# STM32F407layout.net
KiCad netlist of a schematic drawn in EAGLE
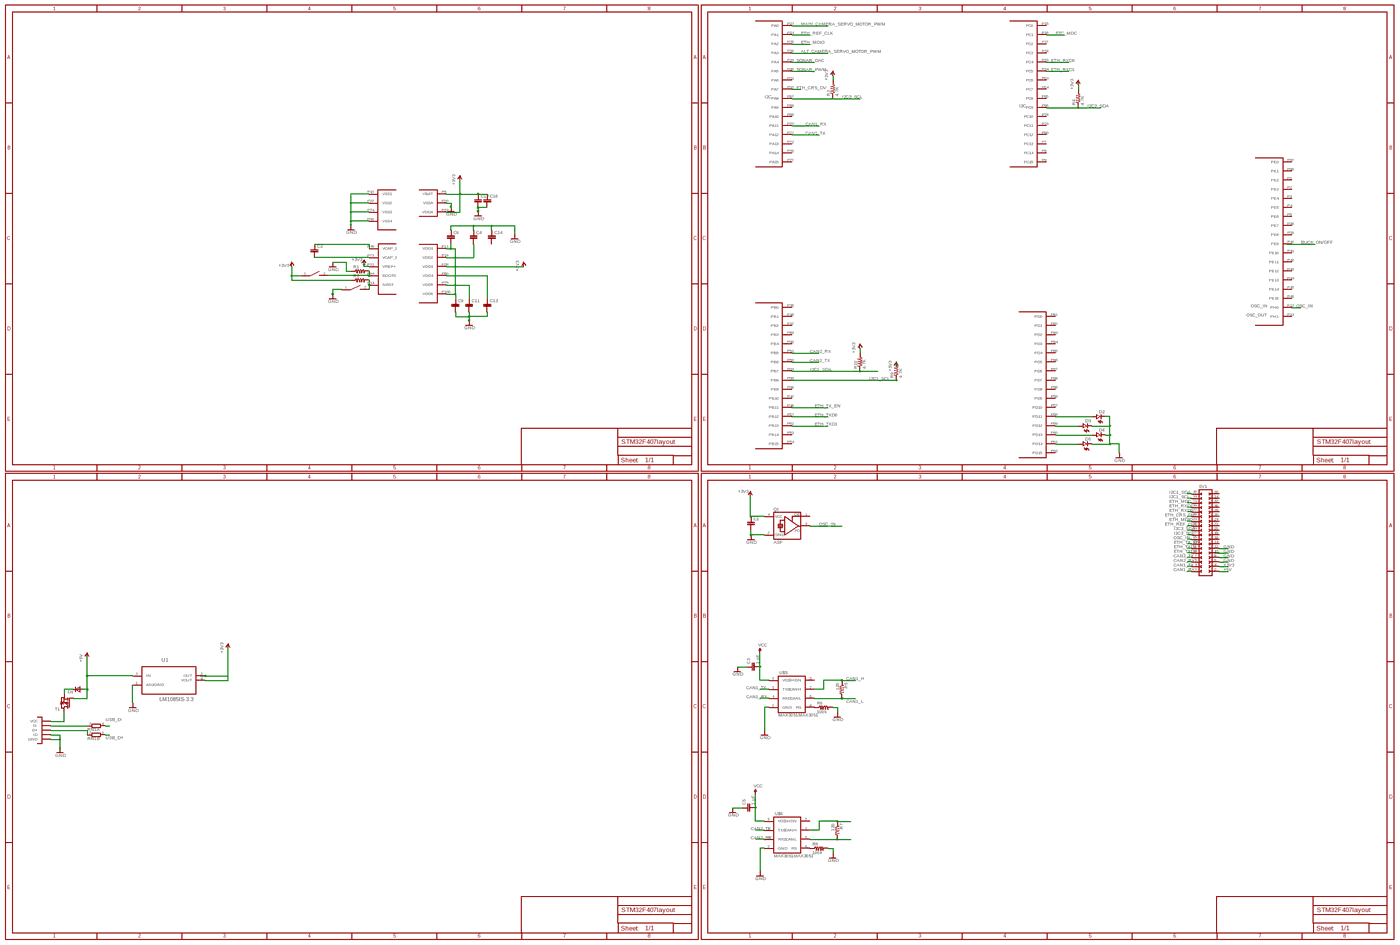
[diagram p0: schematic, sheet 1, overview]
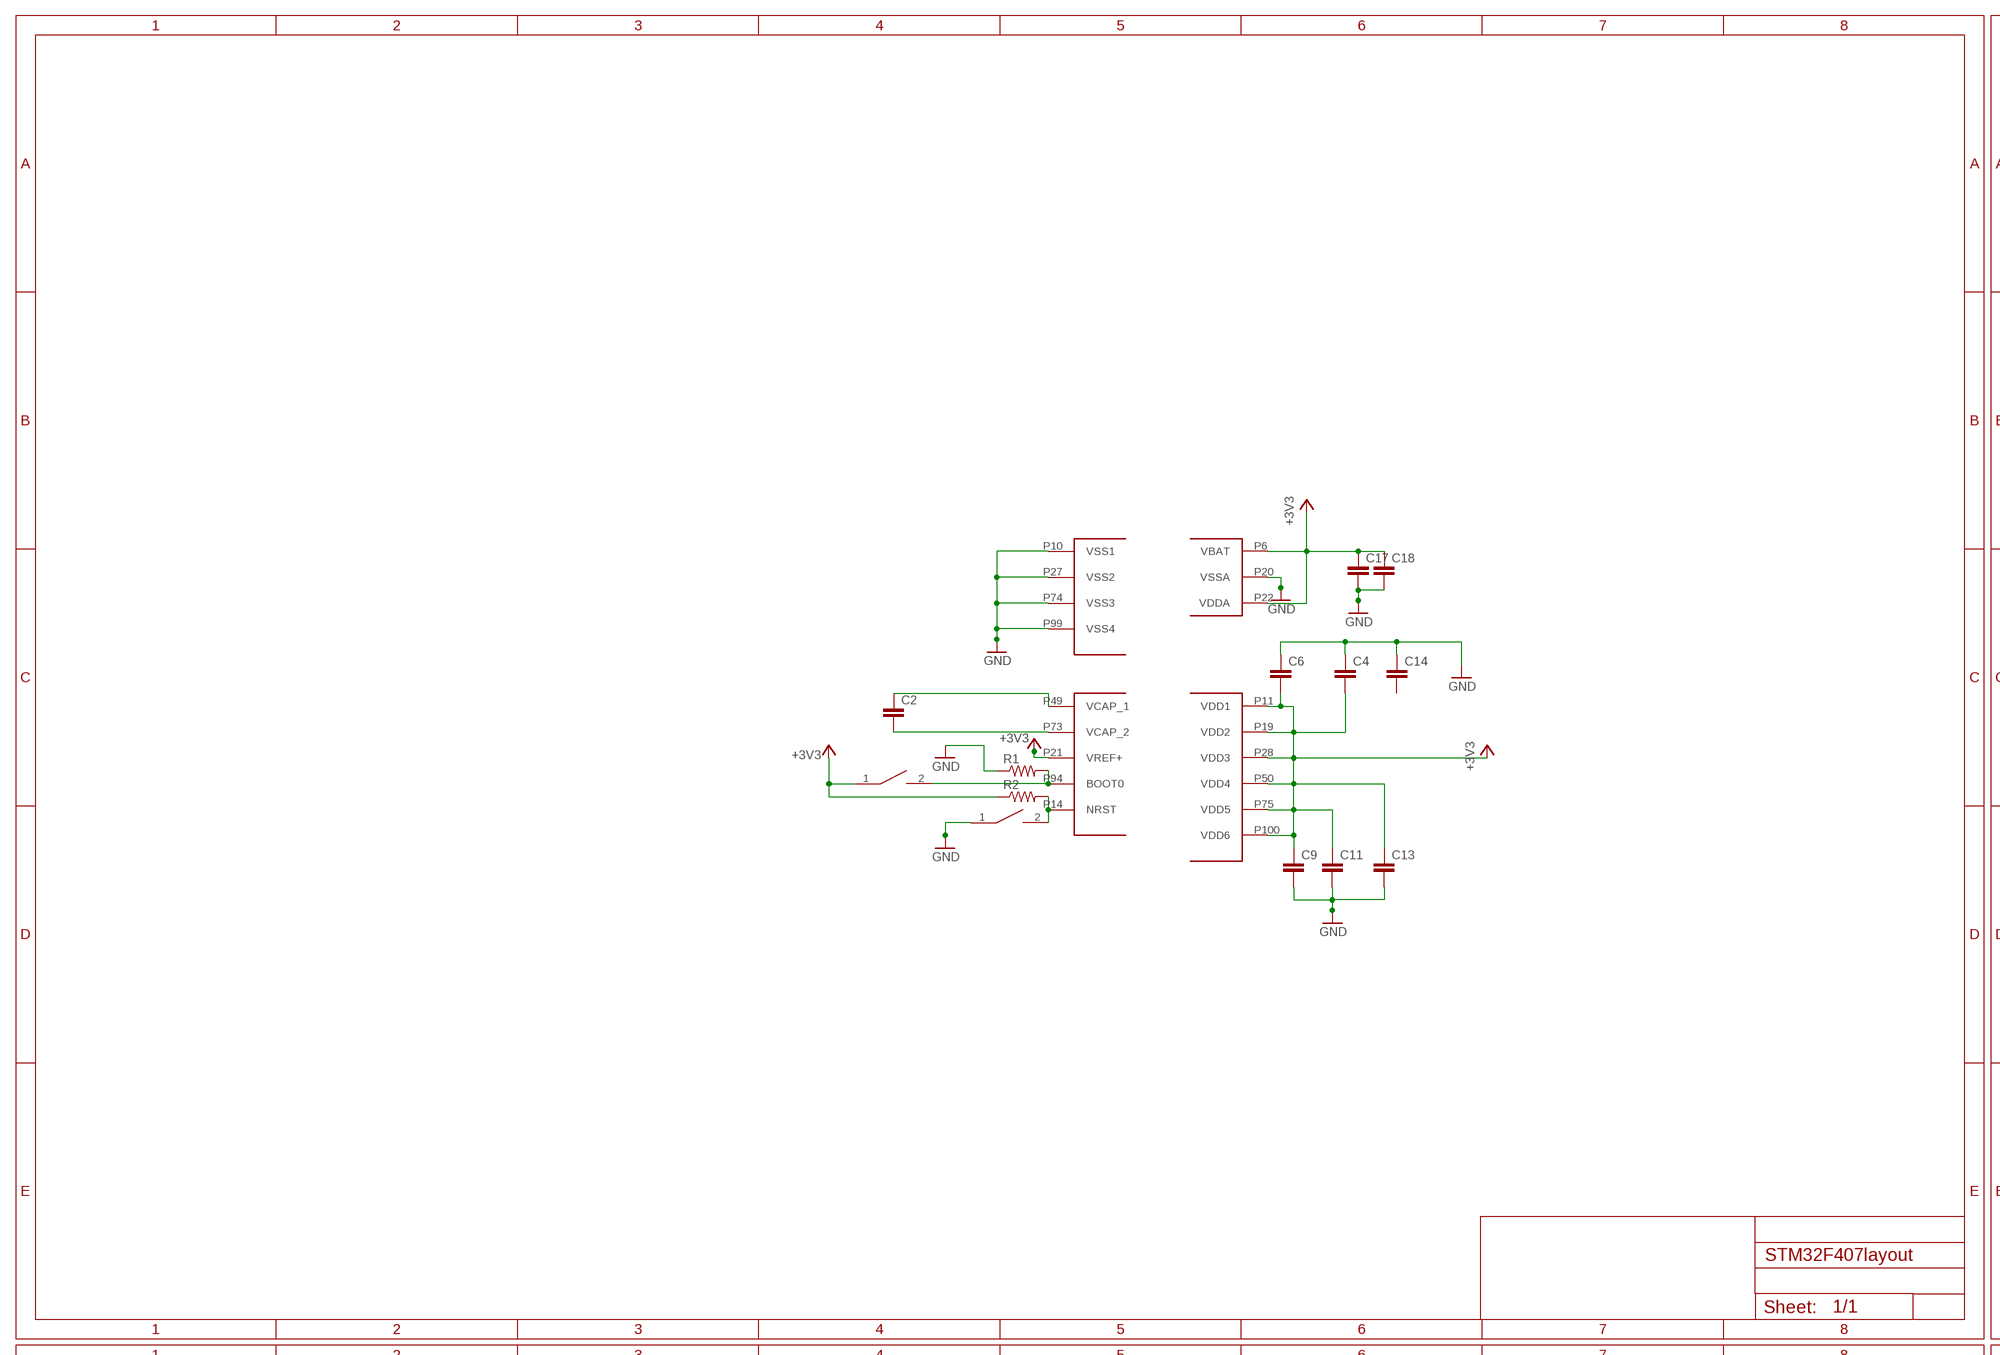
[diagram p1: schematic, sheet 1, part 1 of 4]
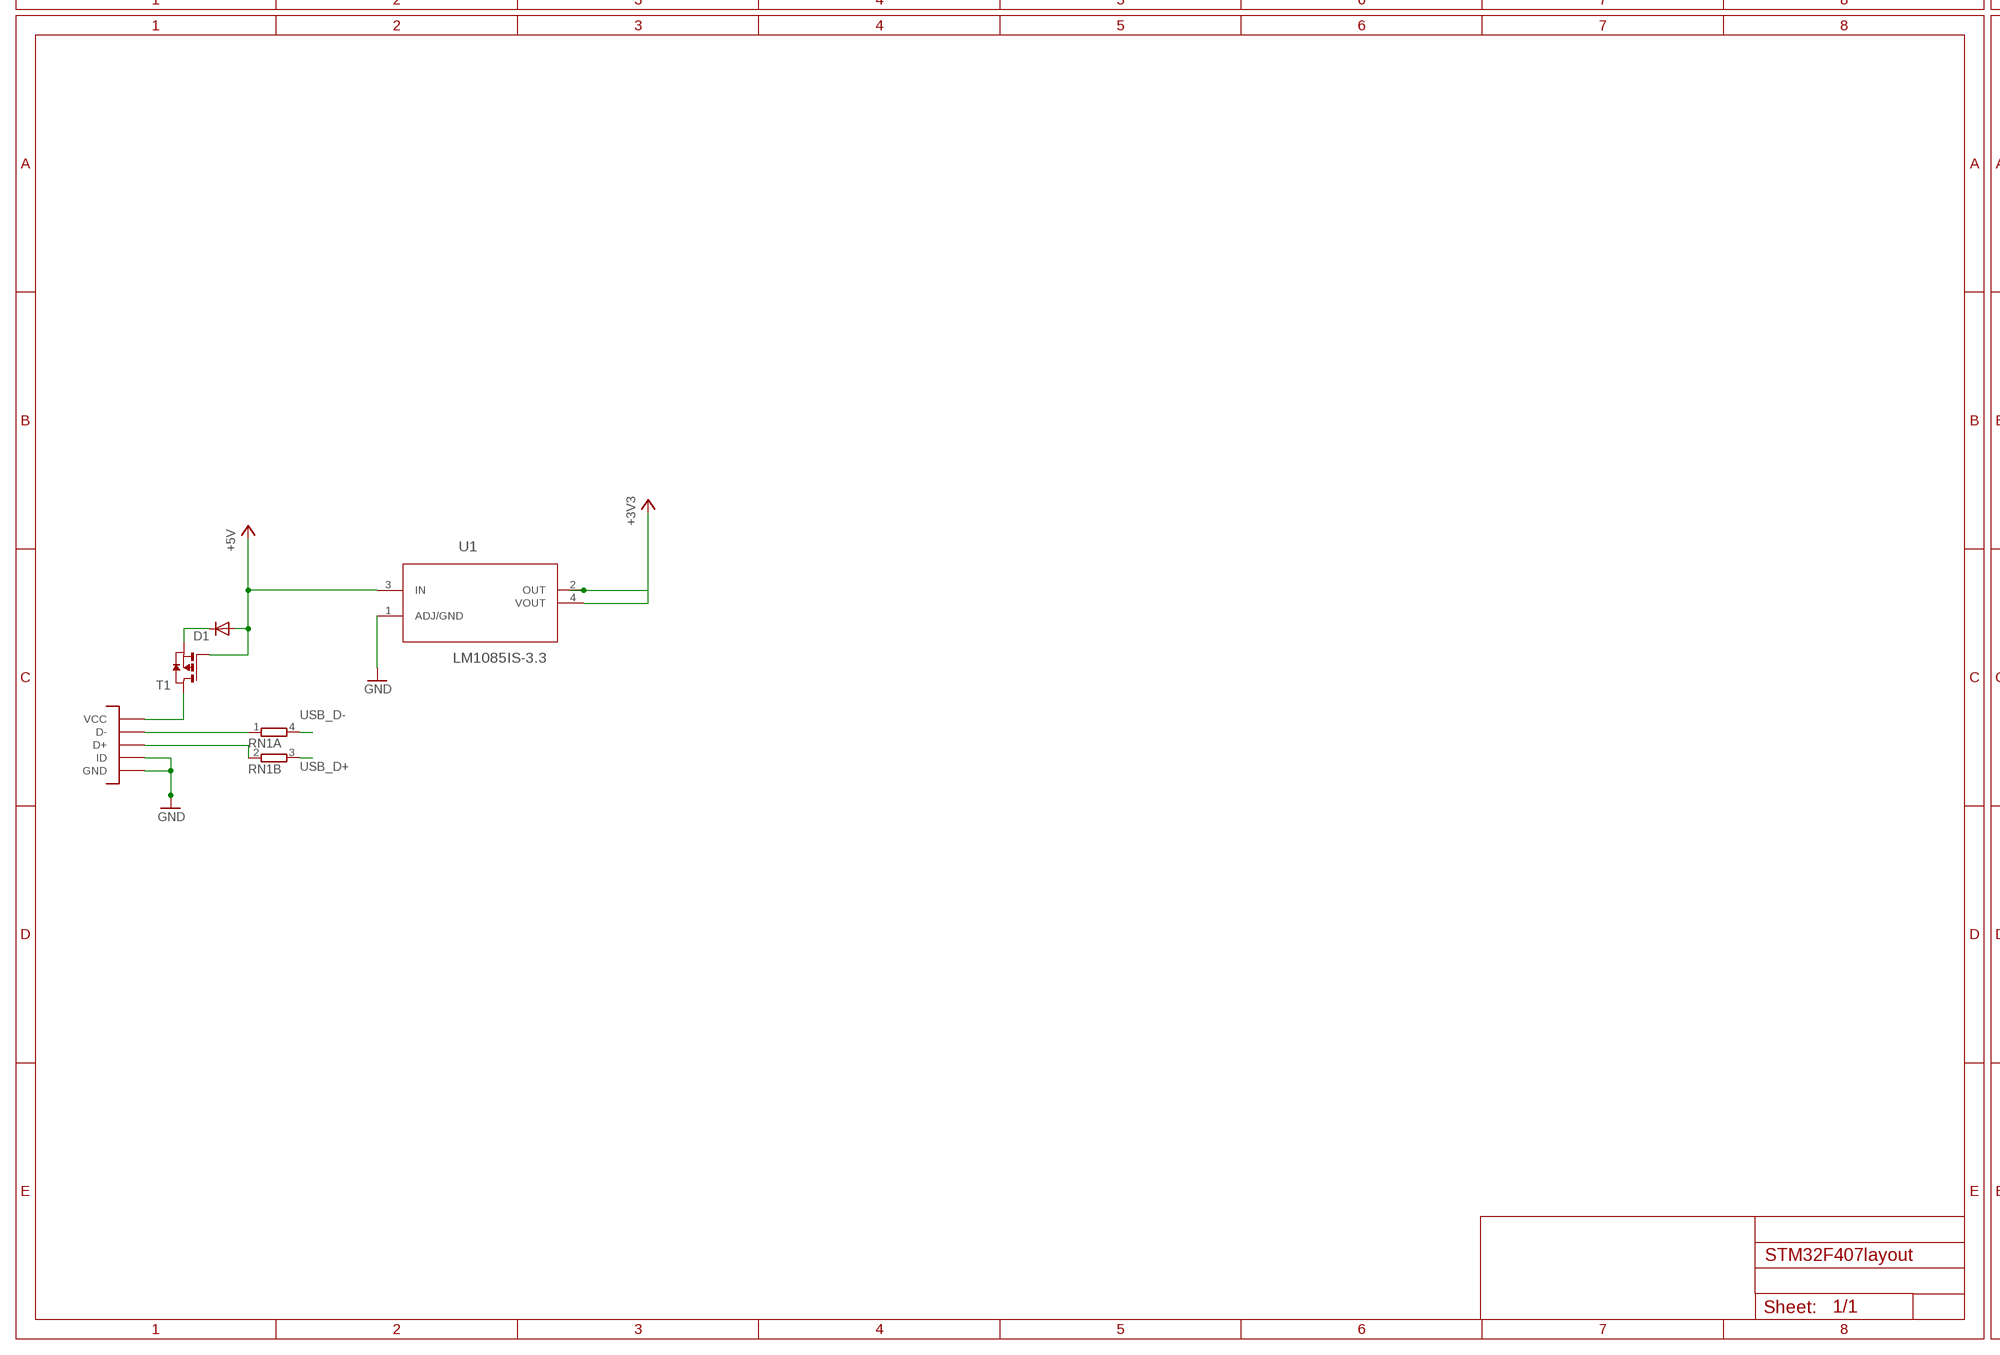
[diagram p2: schematic, sheet 1, part 2 of 4]
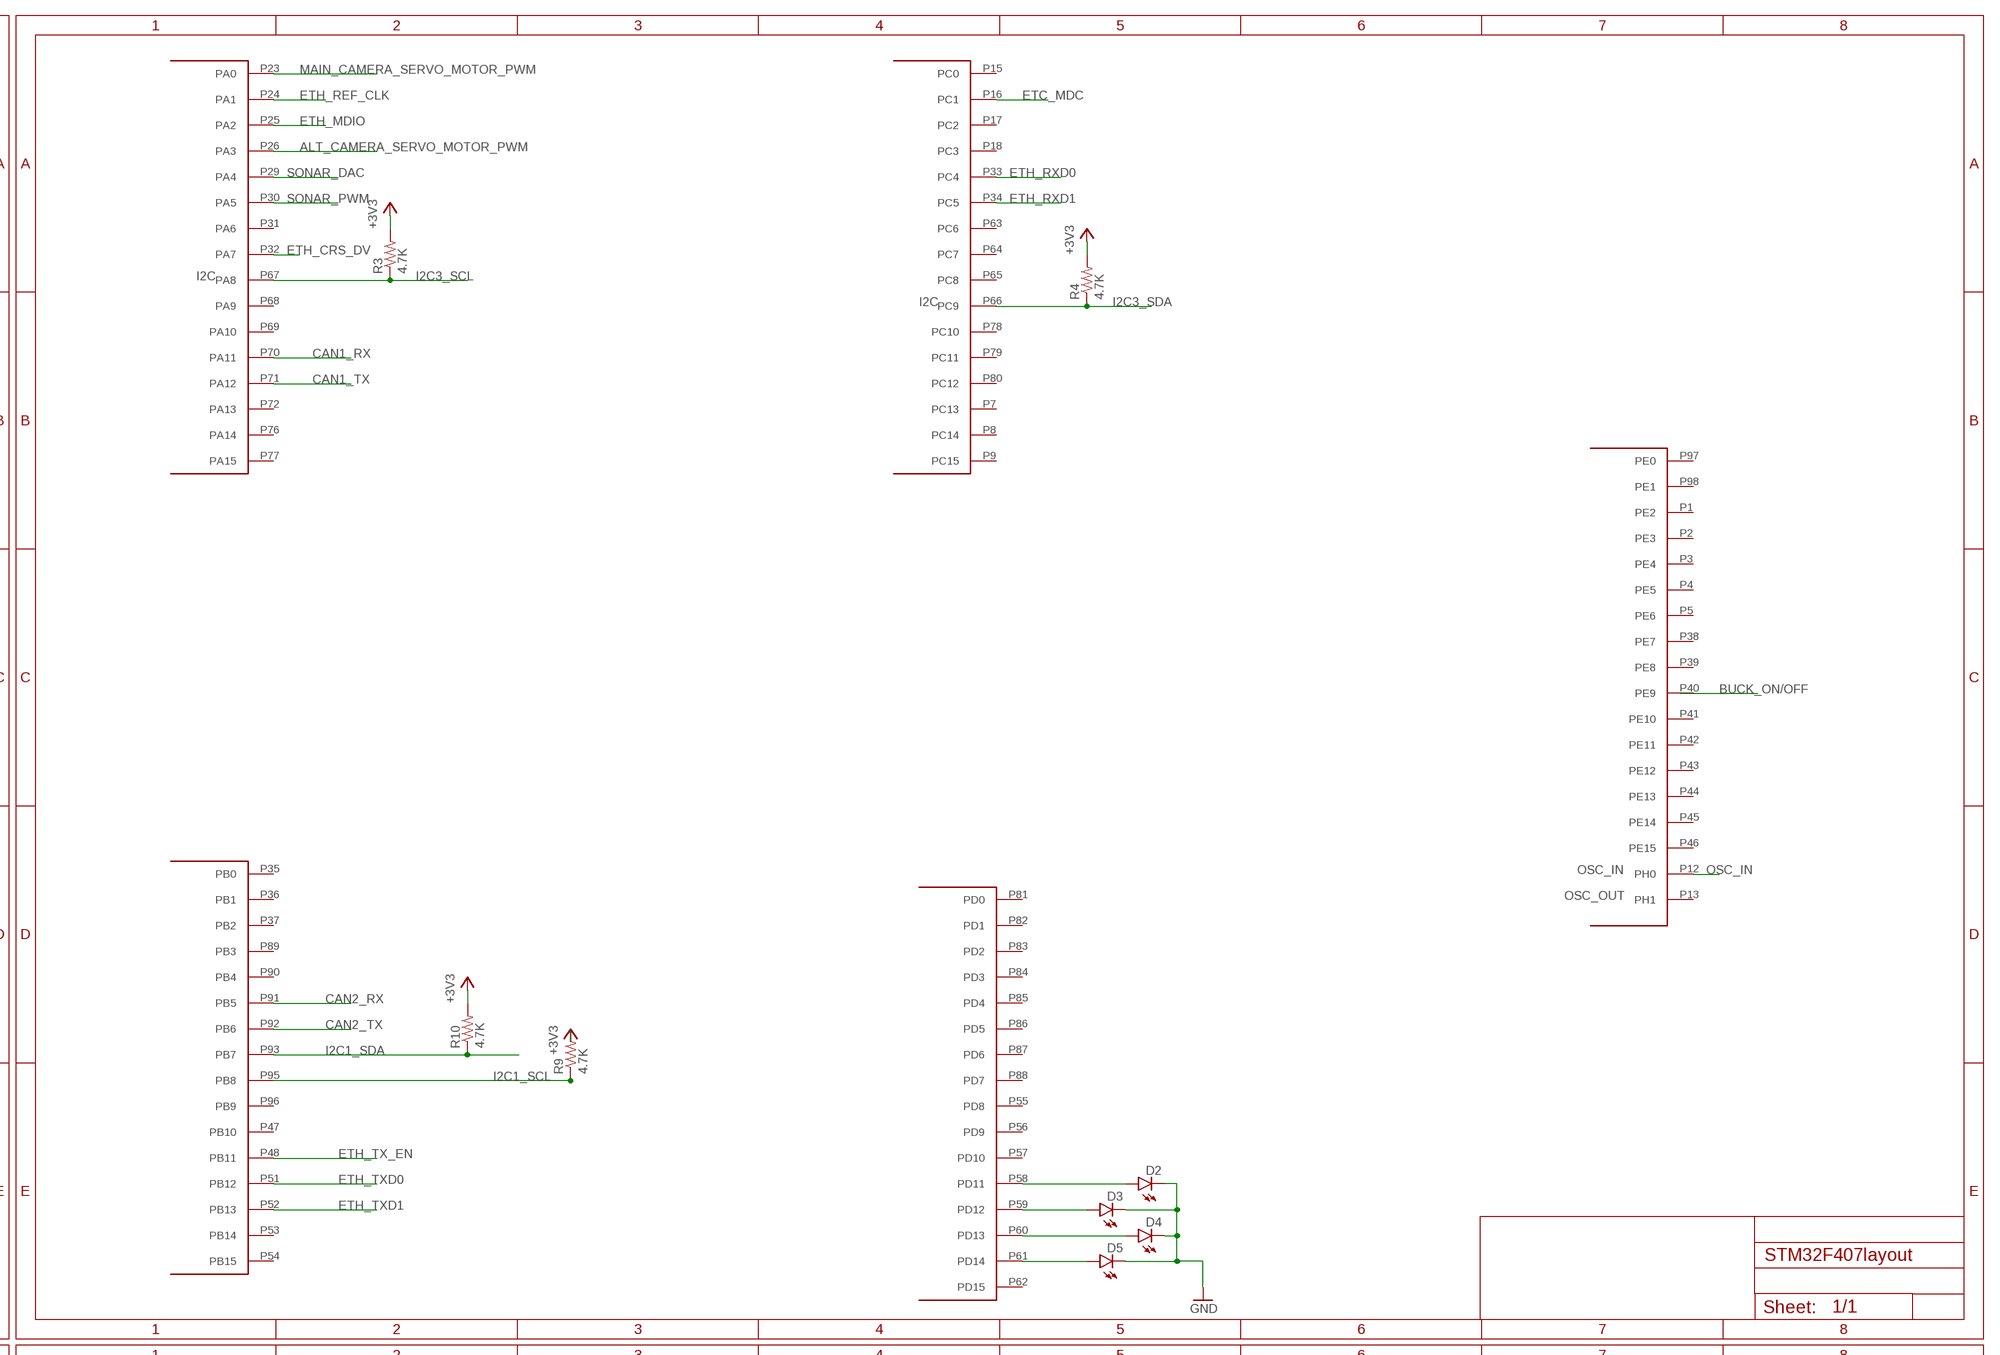
[diagram p3: schematic, sheet 1, part 3 of 4]
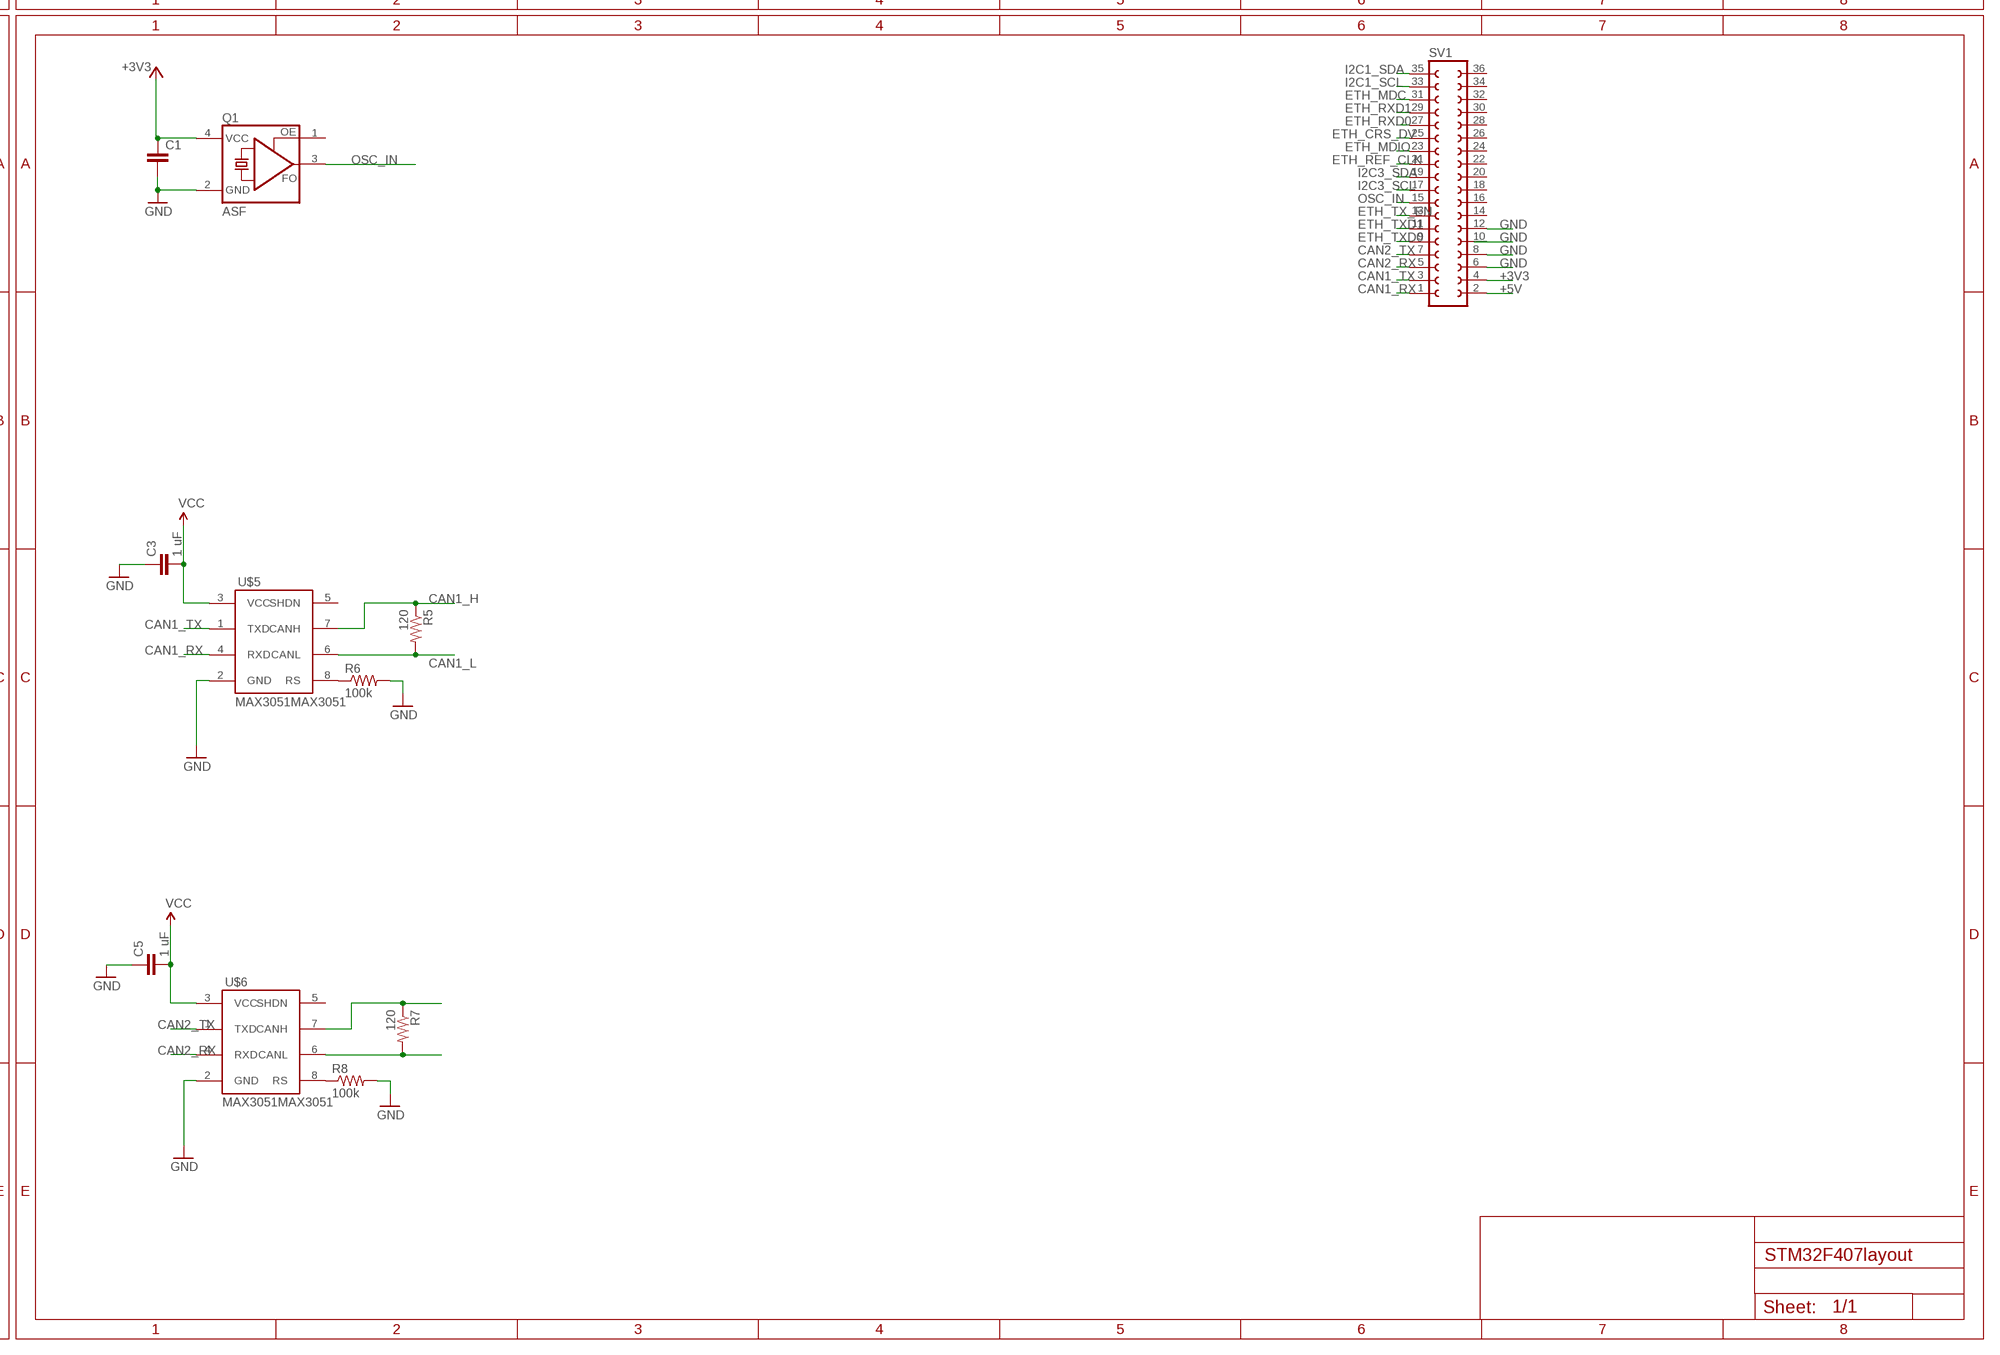
[diagram p4: schematic, sheet 1, part 4 of 4]

(export (version "E")
  (design (tool "Eeschema 10.0.6"))
  (components
    (comp (ref "C1")
      (value "CAP0603-CAP")
      (footprint "eagle-import:0603-CAP")
      (libsource (lib "eagle-import") (part "CAP0603-CAP"))
    )
    (comp (ref "C2")
      (value "CAP0603-CAP")
      (footprint "eagle-import:0603-CAP")
      (libsource (lib "eagle-import") (part "CAP0603-CAP"))
    )
    (comp (ref "C3")
      (value "1 uF")
      (footprint "eagle-import:C2.5-3")
      (libsource (lib "eagle-import") (part "C2,5-3"))
    )
    (comp (ref "C4")
      (value "CAP0603-CAP")
      (footprint "eagle-import:0603-CAP")
      (libsource (lib "eagle-import") (part "CAP0603-CAP"))
    )
    (comp (ref "C5")
      (value "1 uF")
      (footprint "eagle-import:C2.5-3")
      (libsource (lib "eagle-import") (part "C2,5-3"))
    )
    (comp (ref "C6")
      (value "CAP0603-CAP")
      (footprint "eagle-import:0603-CAP")
      (libsource (lib "eagle-import") (part "CAP0603-CAP"))
    )
    (comp (ref "C9")
      (value "CAP0603-CAP")
      (footprint "eagle-import:0603-CAP")
      (libsource (lib "eagle-import") (part "CAP0603-CAP"))
    )
    (comp (ref "C11")
      (value "CAP0603-CAP")
      (footprint "eagle-import:0603-CAP")
      (libsource (lib "eagle-import") (part "CAP0603-CAP"))
    )
    (comp (ref "C13")
      (value "CAP0603-CAP")
      (footprint "eagle-import:0603-CAP")
      (libsource (lib "eagle-import") (part "CAP0603-CAP"))
    )
    (comp (ref "C14")
      (value "CAP0603-CAP")
      (footprint "eagle-import:0603-CAP")
      (libsource (lib "eagle-import") (part "CAP0603-CAP"))
    )
    (comp (ref "C17")
      (value "CAP0603-CAP")
      (footprint "eagle-import:0603-CAP")
      (libsource (lib "eagle-import") (part "CAP0603-CAP"))
    )
    (comp (ref "C18")
      (value "CAP0603-CAP")
      (footprint "eagle-import:0603-CAP")
      (libsource (lib "eagle-import") (part "CAP0603-CAP"))
    )
    (comp (ref "D1")
      (value "DIODE-DO-214AC")
      (footprint "eagle-import:DO-214AC")
      (libsource (lib "eagle-import") (part "DIODE-DO-214AC"))
    )
    (comp (ref "D2")
      (value "LED0603")
      (footprint "eagle-import:LED-0603")
      (libsource (lib "eagle-import") (part "LED0603"))
    )
    (comp (ref "D3")
      (value "LED0603")
      (footprint "eagle-import:LED-0603")
      (libsource (lib "eagle-import") (part "LED0603"))
    )
    (comp (ref "D4")
      (value "LED0603")
      (footprint "eagle-import:LED-0603")
      (libsource (lib "eagle-import") (part "LED0603"))
    )
    (comp (ref "D5")
      (value "LED0603")
      (footprint "eagle-import:LED-0603")
      (libsource (lib "eagle-import") (part "LED0603"))
    )
    (comp (ref "Q1")
      (value "ASF")
      (footprint "eagle-import:ASF")
      (libsource (lib "eagle-import") (part "ASF"))
    )
    (comp (ref "R1")
      (value "RESISTOR0603-RES")
      (footprint "eagle-import:0603-RES")
      (libsource (lib "eagle-import") (part "RESISTOR0603-RES"))
    )
    (comp (ref "R2")
      (value "RESISTOR0603-RES")
      (footprint "eagle-import:0603-RES")
      (libsource (lib "eagle-import") (part "RESISTOR0603-RES"))
    )
    (comp (ref "R3")
      (value "4.7K")
      (footprint "eagle-import:0603-RES")
      (libsource (lib "eagle-import") (part "RESISTOR0603-RES"))
    )
    (comp (ref "R4")
      (value "4.7K")
      (footprint "eagle-import:0603-RES")
      (libsource (lib "eagle-import") (part "RESISTOR0603-RES"))
    )
    (comp (ref "R5")
      (value "120")
      (footprint "eagle-import:0204V")
      (libsource (lib "eagle-import") (part "R-US_0204/2V"))
    )
    (comp (ref "R6")
      (value "100k")
      (footprint "eagle-import:0204V")
      (libsource (lib "eagle-import") (part "R-US_0204/2V"))
    )
    (comp (ref "R7")
      (value "120")
      (footprint "eagle-import:0204V")
      (libsource (lib "eagle-import") (part "R-US_0204/2V"))
    )
    (comp (ref "R8")
      (value "100k")
      (footprint "eagle-import:0204V")
      (libsource (lib "eagle-import") (part "R-US_0204/2V"))
    )
    (comp (ref "R9")
      (value "4.7K")
      (footprint "eagle-import:0603-RES")
      (libsource (lib "eagle-import") (part "RESISTOR0603-RES"))
    )
    (comp (ref "R10")
      (value "4.7K")
      (footprint "eagle-import:0603-RES")
      (libsource (lib "eagle-import") (part "RESISTOR0603-RES"))
    )
    (comp (ref "RN1")
      (value "2R-NEXBV4V")
      (footprint "eagle-import:EXBV4V")
      (fields (field (name "MF") "Rohm Semiconductor") (field (name "MPN") "MNR12ERAPJ220"))
      (libsource (lib "eagle-import") (part "2R-NEXBV4V"))
    )
    (comp (ref "SV1")
      (value "FE18-2")
      (footprint "eagle-import:FE18-2")
      (libsource (lib "eagle-import") (part "FE18-2"))
    )
    (comp (ref "T1")
      (value "FDN340P")
      (footprint "eagle-import:SOT-23")
      (libsource (lib "eagle-import") (part "FDN340P"))
    )
    (comp (ref "U$1")
      (value "STM32F4")
      (footprint "eagle-import:LQFP100")
      (libsource (lib "eagle-import") (part "STM32F4"))
    )
    (comp (ref "U$2")
      (value "SWITCH")
      (footprint "eagle-import:SW_2512")
      (libsource (lib "eagle-import") (part "SWITCH"))
    )
    (comp (ref "U$3")
      (value "SWITCH")
      (footprint "eagle-import:SW_2512")
      (libsource (lib "eagle-import") (part "SWITCH"))
    )
    (comp (ref "U$4")
      (value "MICROUSB")
      (footprint "eagle-import:MICRO_B")
      (libsource (lib "eagle-import") (part "MICROUSB"))
    )
    (comp (ref "U$5")
      (value "MAX3051MAX3051")
      (footprint "eagle-import:SOT23-8L")
      (libsource (lib "eagle-import") (part "MAX3051MAX3051"))
    )
    (comp (ref "U$6")
      (value "MAX3051MAX3051")
      (footprint "eagle-import:SOT23-8L")
      (libsource (lib "eagle-import") (part "MAX3051MAX3051"))
    )
    (comp (ref "U1")
      (value "LM1085IS-3.3")
      (footprint "eagle-import:TO254P1435X457-3N")
      (libsource (lib "eagle-import") (part "LM1085IS-3.3"))
    )
  )
  (nets
    (net (code "1") (name "+3V3") (class "Default")
      (node (ref "C11") (pin "1") (pinfunction "1_1") (pintype "passive"))
      (node (ref "C13") (pin "1") (pinfunction "1_1") (pintype "passive"))
      (node (ref "C17") (pin "1") (pinfunction "1_1") (pintype "passive"))
      (node (ref "C18") (pin "1") (pinfunction "1_1") (pintype "passive"))
      (node (ref "C4") (pin "2") (pinfunction "2_2") (pintype "passive"))
      (node (ref "C6") (pin "2") (pinfunction "2_2") (pintype "passive"))
      (node (ref "C9") (pin "1") (pinfunction "1_1") (pintype "passive"))
      (node (ref "R10") (pin "2") (pinfunction "2_2") (pintype "passive"))
      (node (ref "R2") (pin "1") (pinfunction "1_1") (pintype "passive"))
      (node (ref "R3") (pin "2") (pinfunction "2_2") (pintype "passive"))
      (node (ref "R4") (pin "2") (pinfunction "2_2") (pintype "passive"))
      (node (ref "R9") (pin "2") (pinfunction "2_2") (pintype "passive"))
      (node (ref "SV1") (pin "4") (pinfunction "4_4") (pintype "passive"))
      (node (ref "U$1") (pin "P100") (pinfunction "VDD6_P100") (pintype "bidirectional"))
      (node (ref "U$1") (pin "P11") (pinfunction "VDD1_P11") (pintype "bidirectional"))
      (node (ref "U$1") (pin "P19") (pinfunction "VDD2_P19") (pintype "bidirectional"))
      (node (ref "U$1") (pin "P21") (pinfunction "VREF+_P21") (pintype "bidirectional"))
      (node (ref "U$1") (pin "P22") (pinfunction "VDDA_P22") (pintype "bidirectional"))
      (node (ref "U$1") (pin "P28") (pinfunction "VDD3_P28") (pintype "bidirectional"))
      (node (ref "U$1") (pin "P50") (pinfunction "VDD4_P50") (pintype "bidirectional"))
      (node (ref "U$1") (pin "P6") (pinfunction "VBAT_P6") (pintype "bidirectional"))
      (node (ref "U$1") (pin "P75") (pinfunction "VDD5_P75") (pintype "bidirectional"))
      (node (ref "U$3") (pin "1") (pinfunction "P$1_1") (pintype "bidirectional"))
      (node (ref "U1") (pin "2") (pinfunction "OUT_2") (pintype "output"))
      (node (ref "U1") (pin "4") (pinfunction "VOUT_4") (pintype "output"))
    )
    (net (code "2") (name "+5V") (class "Default")
      (node (ref "D1") (pin "A") (pinfunction "A_A") (pintype "passive"))
      (node (ref "SV1") (pin "2") (pinfunction "2_2") (pintype "passive"))
      (node (ref "T1") (pin "3") (pinfunction "G_3") (pintype "passive"))
      (node (ref "U1") (pin "3") (pinfunction "IN_3") (pintype "power_in"))
    )
    (net (code "3") (name "/ALT_CAMERA_SERVO_MOTOR_PWM") (class "Default")
      (node (ref "U$1") (pin "P26") (pinfunction "PA3_P26") (pintype "bidirectional"))
    )
    (net (code "5") (name "/CAN1_H") (class "Default")
      (node (ref "R5") (pin "1") (pinfunction "1_1") (pintype "passive"))
      (node (ref "U$5") (pin "7") (pinfunction "CANH_7") (pintype "bidirectional"))
    )
    (net (code "6") (name "/CAN1_L") (class "Default")
      (node (ref "R5") (pin "2") (pinfunction "2_2") (pintype "passive"))
      (node (ref "U$5") (pin "6") (pinfunction "CANL_6") (pintype "bidirectional"))
    )
    (net (code "7") (name "/CAN1_RX") (class "Default")
      (node (ref "RN1") (pin "4") (pinfunction "2_4") (pintype "passive"))
      (node (ref "SV1") (pin "1") (pinfunction "1_1") (pintype "passive"))
      (node (ref "U$1") (pin "P70") (pinfunction "PA11_P70") (pintype "bidirectional"))
      (node (ref "U$5") (pin "4") (pinfunction "RXD_4") (pintype "bidirectional"))
    )
    (net (code "8") (name "/CAN1_TX") (class "Default")
      (node (ref "RN1") (pin "3") (pinfunction "2_3") (pintype "passive"))
      (node (ref "SV1") (pin "3") (pinfunction "3_3") (pintype "passive"))
      (node (ref "U$1") (pin "P71") (pinfunction "PA12_P71") (pintype "bidirectional"))
      (node (ref "U$5") (pin "1") (pinfunction "TXD_1") (pintype "bidirectional"))
    )
    (net (code "9") (name "/CAN2_RX") (class "Default")
      (node (ref "SV1") (pin "5") (pinfunction "5_5") (pintype "passive"))
      (node (ref "U$1") (pin "P91") (pinfunction "PB5_P91") (pintype "bidirectional"))
      (node (ref "U$6") (pin "4") (pinfunction "RXD_4") (pintype "bidirectional"))
    )
    (net (code "10") (name "/CAN2_TX") (class "Default")
      (node (ref "SV1") (pin "7") (pinfunction "7_7") (pintype "passive"))
      (node (ref "U$1") (pin "P92") (pinfunction "PB6_P92") (pintype "bidirectional"))
      (node (ref "U$6") (pin "1") (pinfunction "TXD_1") (pintype "bidirectional"))
    )
    (net (code "11") (name "/ETC_MDC") (class "Default")
      (node (ref "U$1") (pin "P16") (pinfunction "PC1_P16") (pintype "bidirectional"))
    )
    (net (code "12") (name "/ETH_CRS_DV") (class "Default")
      (node (ref "SV1") (pin "25") (pinfunction "25_25") (pintype "passive"))
      (node (ref "U$1") (pin "P32") (pinfunction "PA7_P32") (pintype "bidirectional"))
    )
    (net (code "13") (name "/ETH_MDC") (class "Default")
      (node (ref "SV1") (pin "31") (pinfunction "31_31") (pintype "passive"))
    )
    (net (code "14") (name "/ETH_MDIO") (class "Default")
      (node (ref "SV1") (pin "23") (pinfunction "23_23") (pintype "passive"))
      (node (ref "U$1") (pin "P25") (pinfunction "PA2_P25") (pintype "bidirectional"))
    )
    (net (code "15") (name "/ETH_REF_CLK") (class "Default")
      (node (ref "SV1") (pin "21") (pinfunction "21_21") (pintype "passive"))
      (node (ref "U$1") (pin "P24") (pinfunction "PA1_P24") (pintype "bidirectional"))
    )
    (net (code "16") (name "/ETH_RXD0") (class "Default")
      (node (ref "SV1") (pin "27") (pinfunction "27_27") (pintype "passive"))
      (node (ref "U$1") (pin "P33") (pinfunction "PC4_P33") (pintype "bidirectional"))
    )
    (net (code "17") (name "/ETH_RXD1") (class "Default")
      (node (ref "SV1") (pin "29") (pinfunction "29_29") (pintype "passive"))
      (node (ref "U$1") (pin "P34") (pinfunction "PC5_P34") (pintype "bidirectional"))
    )
    (net (code "18") (name "/ETH_TXD0") (class "Default")
      (node (ref "SV1") (pin "9") (pinfunction "9_9") (pintype "passive"))
      (node (ref "U$1") (pin "P51") (pinfunction "PB12_P51") (pintype "bidirectional"))
    )
    (net (code "19") (name "/ETH_TXD1") (class "Default")
      (node (ref "SV1") (pin "11") (pinfunction "11_11") (pintype "passive"))
      (node (ref "U$1") (pin "P52") (pinfunction "PB13_P52") (pintype "bidirectional"))
    )
    (net (code "20") (name "/ETH_TX_EN") (class "Default")
      (node (ref "SV1") (pin "13") (pinfunction "13_13") (pintype "passive"))
      (node (ref "U$1") (pin "P48") (pinfunction "PB11_P48") (pintype "bidirectional"))
    )
    (net (code "21") (name "/I2C1_SCL") (class "Default")
      (node (ref "R9") (pin "1") (pinfunction "1_1") (pintype "passive"))
      (node (ref "SV1") (pin "33") (pinfunction "33_33") (pintype "passive"))
      (node (ref "U$1") (pin "P95") (pinfunction "PB8_P95") (pintype "bidirectional"))
    )
    (net (code "22") (name "/I2C1_SDA") (class "Default")
      (node (ref "R10") (pin "1") (pinfunction "1_1") (pintype "passive"))
      (node (ref "SV1") (pin "35") (pinfunction "35_35") (pintype "passive"))
      (node (ref "U$1") (pin "P93") (pinfunction "PB7_P93") (pintype "bidirectional"))
    )
    (net (code "23") (name "/I2C3_SCL") (class "Default")
      (node (ref "R3") (pin "1") (pinfunction "1_1") (pintype "passive"))
      (node (ref "SV1") (pin "17") (pinfunction "17_17") (pintype "passive"))
      (node (ref "U$1") (pin "P67") (pinfunction "PA8_P67") (pintype "bidirectional"))
    )
    (net (code "24") (name "/I2C3_SDA") (class "Default")
      (node (ref "R4") (pin "1") (pinfunction "1_1") (pintype "passive"))
      (node (ref "SV1") (pin "19") (pinfunction "19_19") (pintype "passive"))
      (node (ref "U$1") (pin "P66") (pinfunction "PC9_P66") (pintype "bidirectional"))
    )
    (net (code "25") (name "/MAIN_CAMERA_SERVO_MOTOR_PWM") (class "Default")
      (node (ref "U$1") (pin "P23") (pinfunction "PA0_P23") (pintype "bidirectional"))
    )
    (net (code "26") (name "/OSC_IN") (class "Default")
      (node (ref "Q1") (pin "3") (pinfunction "FO_3") (pintype "output"))
      (node (ref "SV1") (pin "15") (pinfunction "15_15") (pintype "passive"))
      (node (ref "U$1") (pin "P12") (pinfunction "PH0_P12") (pintype "bidirectional"))
    )
    (net (code "27") (name "/SONAR_DAC") (class "Default")
      (node (ref "U$1") (pin "P29") (pinfunction "PA4_P29") (pintype "bidirectional"))
    )
    (net (code "28") (name "/SONAR_PWM") (class "Default")
      (node (ref "U$1") (pin "P30") (pinfunction "PA5_P30") (pintype "bidirectional"))
    )
    (net (code "29") (name "GND") (class "Default")
      (node (ref "C1") (pin "2") (pinfunction "2_2") (pintype "passive"))
      (node (ref "C11") (pin "2") (pinfunction "2_2") (pintype "passive"))
      (node (ref "C13") (pin "2") (pinfunction "2_2") (pintype "passive"))
      (node (ref "C14") (pin "1") (pinfunction "1_1") (pintype "passive"))
      (node (ref "C17") (pin "2") (pinfunction "2_2") (pintype "passive"))
      (node (ref "C18") (pin "2") (pinfunction "2_2") (pintype "passive"))
      (node (ref "C3") (pin "1") (pinfunction "1_1") (pintype "passive"))
      (node (ref "C4") (pin "1") (pinfunction "1_1") (pintype "passive"))
      (node (ref "C5") (pin "1") (pinfunction "1_1") (pintype "passive"))
      (node (ref "C6") (pin "1") (pinfunction "1_1") (pintype "passive"))
      (node (ref "C9") (pin "2") (pinfunction "2_2") (pintype "passive"))
      (node (ref "D2") (pin "C") (pinfunction "C_C") (pintype "passive"))
      (node (ref "D3") (pin "C") (pinfunction "C_C") (pintype "passive"))
      (node (ref "D4") (pin "C") (pinfunction "C_C") (pintype "passive"))
      (node (ref "D5") (pin "C") (pinfunction "C_C") (pintype "passive"))
      (node (ref "Q1") (pin "2") (pinfunction "GND_2") (pintype "power_in"))
      (node (ref "R1") (pin "1") (pinfunction "1_1") (pintype "passive"))
      (node (ref "R6") (pin "2") (pinfunction "2_2") (pintype "passive"))
      (node (ref "R8") (pin "2") (pinfunction "2_2") (pintype "passive"))
      (node (ref "SV1") (pin "12") (pinfunction "12_12") (pintype "passive"))
      (node (ref "SV1") (pin "6") (pinfunction "6_6") (pintype "passive"))
      (node (ref "SV1") (pin "8") (pinfunction "8_8") (pintype "passive"))
      (node (ref "U$1") (pin "P10") (pinfunction "VSS1_P10") (pintype "bidirectional"))
      (node (ref "U$1") (pin "P20") (pinfunction "VSSA_P20") (pintype "bidirectional"))
      (node (ref "U$1") (pin "P27") (pinfunction "VSS2_P27") (pintype "bidirectional"))
      (node (ref "U$1") (pin "P74") (pinfunction "VSS3_P74") (pintype "bidirectional"))
      (node (ref "U$1") (pin "P99") (pinfunction "VSS4_P99") (pintype "bidirectional"))
      (node (ref "U$2") (pin "1") (pinfunction "P$1_1") (pintype "bidirectional"))
      (node (ref "U$4") (pin "GND1") (pinfunction "GND_GND1") (pintype "bidirectional"))
      (node (ref "U$4") (pin "GND2") (pinfunction "GND_GND2") (pintype "bidirectional"))
      (node (ref "U$4") (pin "GND3") (pinfunction "GND_GND3") (pintype "bidirectional"))
      (node (ref "U$4") (pin "GND4") (pinfunction "GND_GND4") (pintype "bidirectional"))
      (node (ref "U$4") (pin "GND7") (pinfunction "GND_GND7") (pintype "bidirectional"))
      (node (ref "U$4") (pin "GND8") (pinfunction "GND_GND8") (pintype "bidirectional"))
      (node (ref "U$4") (pin "P4") (pinfunction "ID_P4") (pintype "bidirectional"))
      (node (ref "U$4") (pin "P5") (pinfunction "GND_P5") (pintype "bidirectional"))
      (node (ref "U$5") (pin "2") (pinfunction "GND_2") (pintype "bidirectional"))
      (node (ref "U$6") (pin "2") (pinfunction "GND_2") (pintype "bidirectional"))
      (node (ref "U1") (pin "1") (pinfunction "ADJ/GND_1") (pintype "passive"))
    )
    (net (code "30") (name "Net-(Q1-VCC)") (class "Default")
      (node (ref "C1") (pin "1") (pinfunction "1_1") (pintype "passive"))
      (node (ref "Q1") (pin "4") (pinfunction "VCC_4") (pintype "power_in"))
    )
    (net (code "31") (name "Net-(RN1B-1)") (class "Default")
      (node (ref "RN1") (pin "2") (pinfunction "1_2") (pintype "passive"))
      (node (ref "U$4") (pin "P3") (pinfunction "D+_P3") (pintype "bidirectional"))
    )
    (net (code "32") (name "Net-(T1-D)") (class "Default")
      (node (ref "T1") (pin "1") (pinfunction "D_1") (pintype "passive"))
      (node (ref "U$4") (pin "P1") (pinfunction "VCC_P1") (pintype "bidirectional"))
    )
    (net (code "33") (name "Net-(T1-S)") (class "Default")
      (node (ref "D1") (pin "C") (pinfunction "C_C") (pintype "passive"))
      (node (ref "T1") (pin "2") (pinfunction "S_2") (pintype "passive"))
    )
    (net (code "34") (name "Net-(U$1D-PD11)") (class "Default")
      (node (ref "D2") (pin "A") (pinfunction "A_A") (pintype "passive"))
      (node (ref "U$1") (pin "P58") (pinfunction "PD11_P58") (pintype "bidirectional"))
    )
    (net (code "35") (name "Net-(U$1D-PD12)") (class "Default")
      (node (ref "D3") (pin "A") (pinfunction "A_A") (pintype "passive"))
      (node (ref "U$1") (pin "P59") (pinfunction "PD12_P59") (pintype "bidirectional"))
    )
    (net (code "36") (name "Net-(U$1D-PD13)") (class "Default")
      (node (ref "D4") (pin "A") (pinfunction "A_A") (pintype "passive"))
      (node (ref "U$1") (pin "P60") (pinfunction "PD13_P60") (pintype "bidirectional"))
    )
    (net (code "37") (name "Net-(U$1D-PD14)") (class "Default")
      (node (ref "D5") (pin "A") (pinfunction "A_A") (pintype "passive"))
      (node (ref "U$1") (pin "P61") (pinfunction "PD14_P61") (pintype "bidirectional"))
    )
    (net (code "38") (name "Net-(U$1F-BOOT0)") (class "Default")
      (node (ref "R1") (pin "2") (pinfunction "2_2") (pintype "passive"))
      (node (ref "U$1") (pin "P94") (pinfunction "BOOT0_P94") (pintype "bidirectional"))
      (node (ref "U$3") (pin "2") (pinfunction "P$2_2") (pintype "bidirectional"))
    )
    (net (code "39") (name "Net-(U$1F-NRST)") (class "Default")
      (node (ref "R2") (pin "2") (pinfunction "2_2") (pintype "passive"))
      (node (ref "U$1") (pin "P14") (pinfunction "NRST_P14") (pintype "bidirectional"))
      (node (ref "U$2") (pin "2") (pinfunction "P$2_2") (pintype "bidirectional"))
    )
    (net (code "40") (name "Net-(U$1F-VCAP_1)") (class "Default")
      (node (ref "C2") (pin "1") (pinfunction "1_1") (pintype "passive"))
      (node (ref "U$1") (pin "P49") (pinfunction "VCAP_1_P49") (pintype "bidirectional"))
    )
    (net (code "41") (name "Net-(U$1F-VCAP_2)") (class "Default")
      (node (ref "C2") (pin "2") (pinfunction "2_2") (pintype "passive"))
      (node (ref "U$1") (pin "P73") (pinfunction "VCAP_2_P73") (pintype "bidirectional"))
    )
    (net (code "42") (name "Net-(U$4-D-)") (class "Default")
      (node (ref "RN1") (pin "1") (pinfunction "1_1") (pintype "passive"))
      (node (ref "U$4") (pin "P2") (pinfunction "D-_P2") (pintype "bidirectional"))
    )
    (net (code "43") (name "Net-(U$5-RS)") (class "Default")
      (node (ref "R6") (pin "1") (pinfunction "1_1") (pintype "passive"))
      (node (ref "U$5") (pin "8") (pinfunction "RS_8") (pintype "bidirectional"))
    )
    (net (code "44") (name "Net-(U$6-CANH)") (class "Default")
      (node (ref "R7") (pin "1") (pinfunction "1_1") (pintype "passive"))
      (node (ref "U$6") (pin "7") (pinfunction "CANH_7") (pintype "bidirectional"))
    )
    (net (code "45") (name "Net-(U$6-CANL)") (class "Default")
      (node (ref "R7") (pin "2") (pinfunction "2_2") (pintype "passive"))
      (node (ref "U$6") (pin "6") (pinfunction "CANL_6") (pintype "bidirectional"))
    )
    (net (code "46") (name "Net-(U$6-RS)") (class "Default")
      (node (ref "R8") (pin "1") (pinfunction "1_1") (pintype "passive"))
      (node (ref "U$6") (pin "8") (pinfunction "RS_8") (pintype "bidirectional"))
    )
    (net (code "47") (name "VCC") (class "Default")
      (node (ref "C3") (pin "2") (pinfunction "2_2") (pintype "passive"))
      (node (ref "C5") (pin "2") (pinfunction "2_2") (pintype "passive"))
      (node (ref "U$5") (pin "3") (pinfunction "VCC_3") (pintype "bidirectional"))
      (node (ref "U$6") (pin "3") (pinfunction "VCC_3") (pintype "bidirectional"))
    )
    (net (code "48") (name "unconnected-(C14-Pad2)") (class "Default")
      (node (ref "C14") (pin "2") (pinfunction "2_2") (pintype "passive"))
    )
    (net (code "49") (name "unconnected-(Q1-OE-Pad1)") (class "Default")
      (node (ref "Q1") (pin "1") (pinfunction "OE_1") (pintype "input"))
    )
    (net (code "50") (name "unconnected-(SV1-Pad10)") (class "Default")
      (node (ref "SV1") (pin "10") (pinfunction "10_10") (pintype "passive"))
    )
    (net (code "51") (name "unconnected-(SV1-Pad14)") (class "Default")
      (node (ref "SV1") (pin "14") (pinfunction "14_14") (pintype "passive"))
    )
    (net (code "52") (name "unconnected-(SV1-Pad16)") (class "Default")
      (node (ref "SV1") (pin "16") (pinfunction "16_16") (pintype "passive"))
    )
    (net (code "53") (name "unconnected-(SV1-Pad18)") (class "Default")
      (node (ref "SV1") (pin "18") (pinfunction "18_18") (pintype "passive"))
    )
    (net (code "54") (name "unconnected-(SV1-Pad20)") (class "Default")
      (node (ref "SV1") (pin "20") (pinfunction "20_20") (pintype "passive"))
    )
    (net (code "55") (name "unconnected-(SV1-Pad22)") (class "Default")
      (node (ref "SV1") (pin "22") (pinfunction "22_22") (pintype "passive"))
    )
    (net (code "56") (name "unconnected-(SV1-Pad24)") (class "Default")
      (node (ref "SV1") (pin "24") (pinfunction "24_24") (pintype "passive"))
    )
    (net (code "57") (name "unconnected-(SV1-Pad26)") (class "Default")
      (node (ref "SV1") (pin "26") (pinfunction "26_26") (pintype "passive"))
    )
    (net (code "58") (name "unconnected-(SV1-Pad28)") (class "Default")
      (node (ref "SV1") (pin "28") (pinfunction "28_28") (pintype "passive"))
    )
    (net (code "59") (name "unconnected-(SV1-Pad30)") (class "Default")
      (node (ref "SV1") (pin "30") (pinfunction "30_30") (pintype "passive"))
    )
    (net (code "60") (name "unconnected-(SV1-Pad32)") (class "Default")
      (node (ref "SV1") (pin "32") (pinfunction "32_32") (pintype "passive"))
    )
    (net (code "61") (name "unconnected-(SV1-Pad34)") (class "Default")
      (node (ref "SV1") (pin "34") (pinfunction "34_34") (pintype "passive"))
    )
    (net (code "62") (name "unconnected-(SV1-Pad36)") (class "Default")
      (node (ref "SV1") (pin "36") (pinfunction "36_36") (pintype "passive"))
    )
    (net (code "63") (name "unconnected-(U$1A-PA6-PadP31)") (class "Default")
      (node (ref "U$1") (pin "P31") (pinfunction "PA6_P31") (pintype "bidirectional"))
    )
    (net (code "64") (name "unconnected-(U$1A-PA9-PadP68)") (class "Default")
      (node (ref "U$1") (pin "P68") (pinfunction "PA9_P68") (pintype "bidirectional"))
    )
    (net (code "65") (name "unconnected-(U$1A-PA10-PadP69)") (class "Default")
      (node (ref "U$1") (pin "P69") (pinfunction "PA10_P69") (pintype "bidirectional"))
    )
    (net (code "66") (name "unconnected-(U$1A-PA13-PadP72)") (class "Default")
      (node (ref "U$1") (pin "P72") (pinfunction "PA13_P72") (pintype "bidirectional"))
    )
    (net (code "67") (name "unconnected-(U$1A-PA14-PadP76)") (class "Default")
      (node (ref "U$1") (pin "P76") (pinfunction "PA14_P76") (pintype "bidirectional"))
    )
    (net (code "68") (name "unconnected-(U$1A-PA15-PadP77)") (class "Default")
      (node (ref "U$1") (pin "P77") (pinfunction "PA15_P77") (pintype "bidirectional"))
    )
    (net (code "69") (name "unconnected-(U$1B-PB0-PadP35)") (class "Default")
      (node (ref "U$1") (pin "P35") (pinfunction "PB0_P35") (pintype "bidirectional"))
    )
    (net (code "70") (name "unconnected-(U$1B-PB1-PadP36)") (class "Default")
      (node (ref "U$1") (pin "P36") (pinfunction "PB1_P36") (pintype "bidirectional"))
    )
    (net (code "71") (name "unconnected-(U$1B-PB2-PadP37)") (class "Default")
      (node (ref "U$1") (pin "P37") (pinfunction "PB2_P37") (pintype "bidirectional"))
    )
    (net (code "72") (name "unconnected-(U$1B-PB3-PadP89)") (class "Default")
      (node (ref "U$1") (pin "P89") (pinfunction "PB3_P89") (pintype "bidirectional"))
    )
    (net (code "73") (name "unconnected-(U$1B-PB4-PadP90)") (class "Default")
      (node (ref "U$1") (pin "P90") (pinfunction "PB4_P90") (pintype "bidirectional"))
    )
    (net (code "74") (name "unconnected-(U$1B-PB9-PadP96)") (class "Default")
      (node (ref "U$1") (pin "P96") (pinfunction "PB9_P96") (pintype "bidirectional"))
    )
    (net (code "75") (name "unconnected-(U$1B-PB10-PadP47)") (class "Default")
      (node (ref "U$1") (pin "P47") (pinfunction "PB10_P47") (pintype "bidirectional"))
    )
    (net (code "76") (name "unconnected-(U$1B-PB14-PadP53)") (class "Default")
      (node (ref "U$1") (pin "P53") (pinfunction "PB14_P53") (pintype "bidirectional"))
    )
    (net (code "77") (name "unconnected-(U$1B-PB15-PadP54)") (class "Default")
      (node (ref "U$1") (pin "P54") (pinfunction "PB15_P54") (pintype "bidirectional"))
    )
    (net (code "78") (name "unconnected-(U$1C-PC0-PadP15)") (class "Default")
      (node (ref "U$1") (pin "P15") (pinfunction "PC0_P15") (pintype "bidirectional"))
    )
    (net (code "79") (name "unconnected-(U$1C-PC2-PadP17)") (class "Default")
      (node (ref "U$1") (pin "P17") (pinfunction "PC2_P17") (pintype "bidirectional"))
    )
    (net (code "80") (name "unconnected-(U$1C-PC3-PadP18)") (class "Default")
      (node (ref "U$1") (pin "P18") (pinfunction "PC3_P18") (pintype "bidirectional"))
    )
    (net (code "81") (name "unconnected-(U$1C-PC6-PadP63)") (class "Default")
      (node (ref "U$1") (pin "P63") (pinfunction "PC6_P63") (pintype "bidirectional"))
    )
    (net (code "82") (name "unconnected-(U$1C-PC7-PadP64)") (class "Default")
      (node (ref "U$1") (pin "P64") (pinfunction "PC7_P64") (pintype "bidirectional"))
    )
    (net (code "83") (name "unconnected-(U$1C-PC8-PadP65)") (class "Default")
      (node (ref "U$1") (pin "P65") (pinfunction "PC8_P65") (pintype "bidirectional"))
    )
    (net (code "84") (name "unconnected-(U$1C-PC10-PadP78)") (class "Default")
      (node (ref "U$1") (pin "P78") (pinfunction "PC10_P78") (pintype "bidirectional"))
    )
    (net (code "85") (name "unconnected-(U$1C-PC11-PadP79)") (class "Default")
      (node (ref "U$1") (pin "P79") (pinfunction "PC11_P79") (pintype "bidirectional"))
    )
    (net (code "86") (name "unconnected-(U$1C-PC12-PadP80)") (class "Default")
      (node (ref "U$1") (pin "P80") (pinfunction "PC12_P80") (pintype "bidirectional"))
    )
    (net (code "87") (name "unconnected-(U$1C-PC13-PadP7)") (class "Default")
      (node (ref "U$1") (pin "P7") (pinfunction "PC13_P7") (pintype "bidirectional"))
    )
    (net (code "88") (name "unconnected-(U$1C-PC14-PadP8)") (class "Default")
      (node (ref "U$1") (pin "P8") (pinfunction "PC14_P8") (pintype "bidirectional"))
    )
    (net (code "89") (name "unconnected-(U$1C-PC15-PadP9)") (class "Default")
      (node (ref "U$1") (pin "P9") (pinfunction "PC15_P9") (pintype "bidirectional"))
    )
    (net (code "90") (name "unconnected-(U$1D-PD0-PadP81)") (class "Default")
      (node (ref "U$1") (pin "P81") (pinfunction "PD0_P81") (pintype "bidirectional"))
    )
    (net (code "91") (name "unconnected-(U$1D-PD1-PadP82)") (class "Default")
      (node (ref "U$1") (pin "P82") (pinfunction "PD1_P82") (pintype "bidirectional"))
    )
    (net (code "92") (name "unconnected-(U$1D-PD2-PadP83)") (class "Default")
      (node (ref "U$1") (pin "P83") (pinfunction "PD2_P83") (pintype "bidirectional"))
    )
    (net (code "93") (name "unconnected-(U$1D-PD3-PadP84)") (class "Default")
      (node (ref "U$1") (pin "P84") (pinfunction "PD3_P84") (pintype "bidirectional"))
    )
    (net (code "94") (name "unconnected-(U$1D-PD4-PadP85)") (class "Default")
      (node (ref "U$1") (pin "P85") (pinfunction "PD4_P85") (pintype "bidirectional"))
    )
    (net (code "95") (name "unconnected-(U$1D-PD5-PadP86)") (class "Default")
      (node (ref "U$1") (pin "P86") (pinfunction "PD5_P86") (pintype "bidirectional"))
    )
    (net (code "96") (name "unconnected-(U$1D-PD6-PadP87)") (class "Default")
      (node (ref "U$1") (pin "P87") (pinfunction "PD6_P87") (pintype "bidirectional"))
    )
    (net (code "97") (name "unconnected-(U$1D-PD7-PadP88)") (class "Default")
      (node (ref "U$1") (pin "P88") (pinfunction "PD7_P88") (pintype "bidirectional"))
    )
    (net (code "98") (name "unconnected-(U$1D-PD8-PadP55)") (class "Default")
      (node (ref "U$1") (pin "P55") (pinfunction "PD8_P55") (pintype "bidirectional"))
    )
    (net (code "99") (name "unconnected-(U$1D-PD9-PadP56)") (class "Default")
      (node (ref "U$1") (pin "P56") (pinfunction "PD9_P56") (pintype "bidirectional"))
    )
    (net (code "100") (name "unconnected-(U$1D-PD10-PadP57)") (class "Default")
      (node (ref "U$1") (pin "P57") (pinfunction "PD10_P57") (pintype "bidirectional"))
    )
    (net (code "101") (name "unconnected-(U$1D-PD15-PadP62)") (class "Default")
      (node (ref "U$1") (pin "P62") (pinfunction "PD15_P62") (pintype "bidirectional"))
    )
    (net (code "102") (name "unconnected-(U$1E-PE0-PadP97)") (class "Default")
      (node (ref "U$1") (pin "P97") (pinfunction "PE0_P97") (pintype "bidirectional"))
    )
    (net (code "103") (name "unconnected-(U$1E-PE1-PadP98)") (class "Default")
      (node (ref "U$1") (pin "P98") (pinfunction "PE1_P98") (pintype "bidirectional"))
    )
    (net (code "104") (name "unconnected-(U$1E-PE2-PadP1)") (class "Default")
      (node (ref "U$1") (pin "P1") (pinfunction "PE2_P1") (pintype "bidirectional"))
    )
    (net (code "105") (name "unconnected-(U$1E-PE3-PadP2)") (class "Default")
      (node (ref "U$1") (pin "P2") (pinfunction "PE3_P2") (pintype "bidirectional"))
    )
    (net (code "106") (name "unconnected-(U$1E-PE4-PadP3)") (class "Default")
      (node (ref "U$1") (pin "P3") (pinfunction "PE4_P3") (pintype "bidirectional"))
    )
    (net (code "107") (name "unconnected-(U$1E-PE5-PadP4)") (class "Default")
      (node (ref "U$1") (pin "P4") (pinfunction "PE5_P4") (pintype "bidirectional"))
    )
    (net (code "108") (name "unconnected-(U$1E-PE6-PadP5)") (class "Default")
      (node (ref "U$1") (pin "P5") (pinfunction "PE6_P5") (pintype "bidirectional"))
    )
    (net (code "109") (name "unconnected-(U$1E-PE7-PadP38)") (class "Default")
      (node (ref "U$1") (pin "P38") (pinfunction "PE7_P38") (pintype "bidirectional"))
    )
    (net (code "110") (name "unconnected-(U$1E-PE8-PadP39)") (class "Default")
      (node (ref "U$1") (pin "P39") (pinfunction "PE8_P39") (pintype "bidirectional"))
    )
    (net (code "111") (name "unconnected-(U$1E-PE9-PadP40)") (class "Default")
      (node (ref "U$1") (pin "P40") (pinfunction "PE9_P40") (pintype "bidirectional"))
    )
    (net (code "112") (name "unconnected-(U$1E-PE10-PadP41)") (class "Default")
      (node (ref "U$1") (pin "P41") (pinfunction "PE10_P41") (pintype "bidirectional"))
    )
    (net (code "113") (name "unconnected-(U$1E-PE11-PadP42)") (class "Default")
      (node (ref "U$1") (pin "P42") (pinfunction "PE11_P42") (pintype "bidirectional"))
    )
    (net (code "114") (name "unconnected-(U$1E-PE12-PadP43)") (class "Default")
      (node (ref "U$1") (pin "P43") (pinfunction "PE12_P43") (pintype "bidirectional"))
    )
    (net (code "115") (name "unconnected-(U$1E-PE13-PadP44)") (class "Default")
      (node (ref "U$1") (pin "P44") (pinfunction "PE13_P44") (pintype "bidirectional"))
    )
    (net (code "116") (name "unconnected-(U$1E-PE14-PadP45)") (class "Default")
      (node (ref "U$1") (pin "P45") (pinfunction "PE14_P45") (pintype "bidirectional"))
    )
    (net (code "117") (name "unconnected-(U$1E-PE15-PadP46)") (class "Default")
      (node (ref "U$1") (pin "P46") (pinfunction "PE15_P46") (pintype "bidirectional"))
    )
    (net (code "118") (name "unconnected-(U$1E-PH1-PadP13)") (class "Default")
      (node (ref "U$1") (pin "P13") (pinfunction "PH1_P13") (pintype "bidirectional"))
    )
    (net (code "119") (name "unconnected-(U$5-SHDN-Pad5)") (class "Default")
      (node (ref "U$5") (pin "5") (pinfunction "SHDN_5") (pintype "bidirectional"))
    )
    (net (code "120") (name "unconnected-(U$6-SHDN-Pad5)") (class "Default")
      (node (ref "U$6") (pin "5") (pinfunction "SHDN_5") (pintype "bidirectional"))
    )
  )
)
